# Sensors_AFE2.net
KiCad netlist of a schematic drawn in Altium Designer
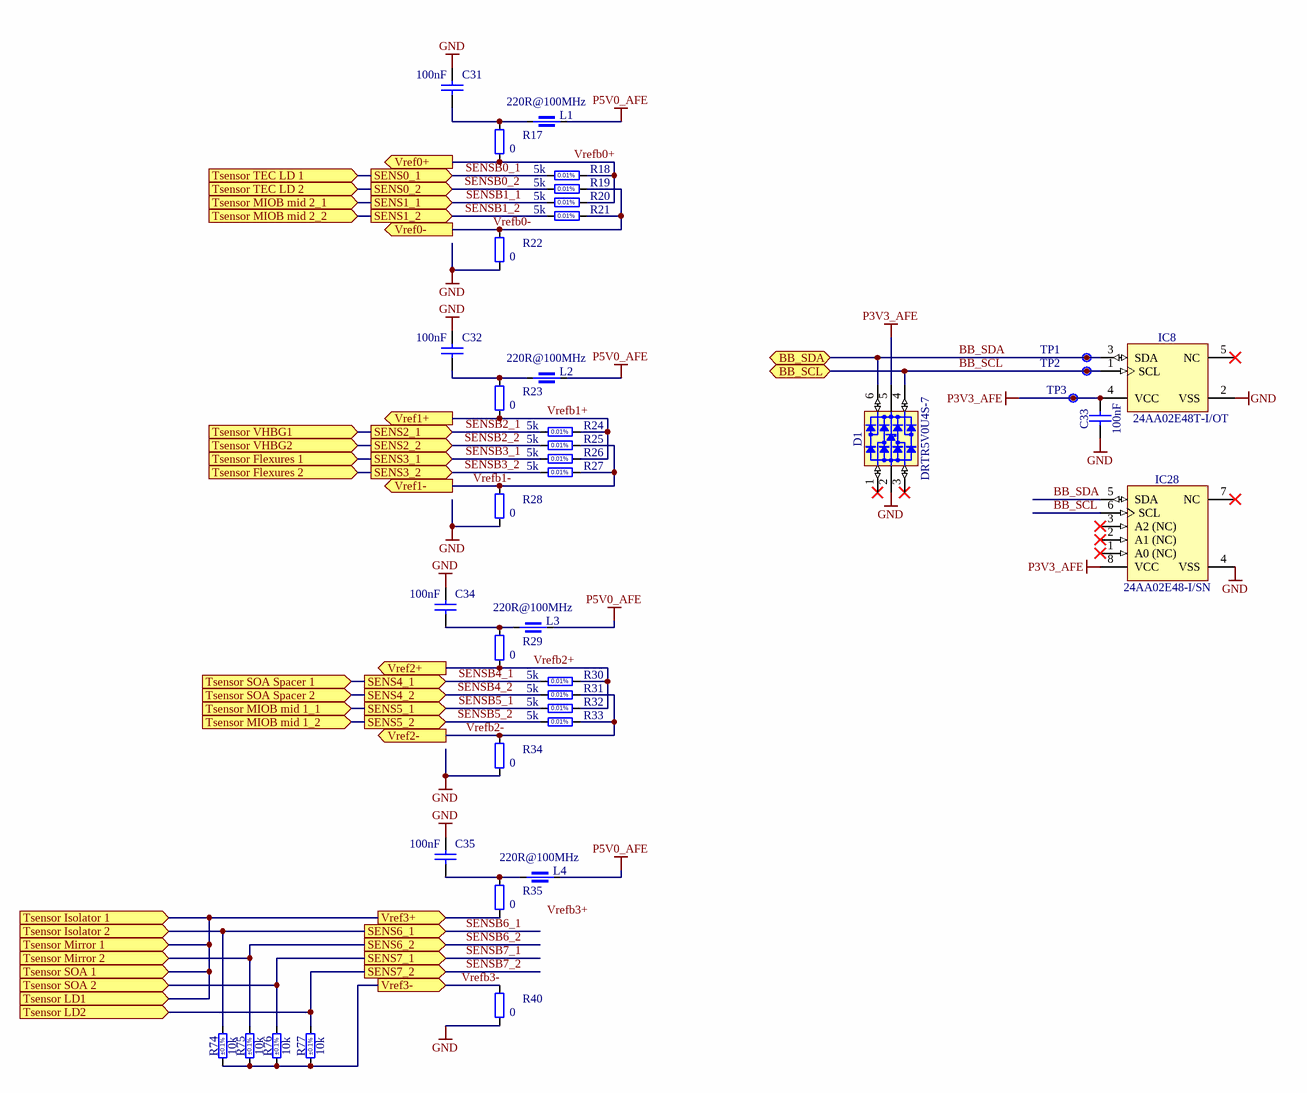
[diagram p0: Sensors_AFE2.schdoc]

(export (version "E")
  (design (tool "Eeschema 10.0.6"))
  (components
    (comp (ref "C31")
      (value "100nF")
      (footprint "CAPC1005X55N")
      (description "Non-polarised capacitor")
      (fields
        (field (name "PART NUMBER") "CC0402_100NF_16V_10%_X5R")
        (field (name "VOLTAGE") "16V")
        (field (name "AUTHOR") "CERN DEM JLC")
      )
      (libsource (lib "Capacitors") (part "Capacitor - non polarized"))
    )
    (comp (ref "C32")
      (value "100nF")
      (footprint "CAPC1005X55N")
      (description "Non-polarised capacitor")
      (fields
        (field (name "PART NUMBER") "CC0402_100NF_16V_10%_X5R")
        (field (name "VOLTAGE") "16V")
        (field (name "AUTHOR") "CERN DEM JLC")
      )
      (libsource (lib "Capacitors") (part "Capacitor - non polarized"))
    )
    (comp (ref "C33")
      (value "100nF")
      (footprint "CAPC1005X55N")
      (description "Non-polarised capacitor")
      (fields
        (field (name "PART NUMBER") "CC0402_100NF_16V_10%_X5R")
        (field (name "VOLTAGE") "16V")
        (field (name "AUTHOR") "CERN DEM JLC")
      )
      (libsource (lib "Capacitors") (part "Capacitor - non polarized"))
    )
    (comp (ref "C34")
      (value "100nF")
      (footprint "CAPC1005X55N")
      (description "Non-polarised capacitor")
      (fields
        (field (name "PART NUMBER") "CC0402_100NF_16V_10%_X5R")
        (field (name "VOLTAGE") "16V")
        (field (name "AUTHOR") "CERN DEM JLC")
      )
      (libsource (lib "Capacitors") (part "Capacitor - non polarized"))
    )
    (comp (ref "C35")
      (value "100nF")
      (footprint "CAPC1005X55N")
      (description "Non-polarised capacitor")
      (fields
        (field (name "PART NUMBER") "CC0402_100NF_16V_10%_X5R")
        (field (name "VOLTAGE") "16V")
        (field (name "AUTHOR") "CERN DEM JLC")
      )
      (libsource (lib "Capacitors") (part "Capacitor - non polarized"))
    )
    (comp (ref "D1")
      (value "DRTR5V0U4S-7")
      (footprint "SOT65P210X110-6N")
      (description "Integrated Quad Ultra-Low Capacitance ESD Protection")
      (fields (field (name "MANUFACTURER") "DIODES") (field (name "AUTHOR") "GK"))
      (libsource (lib "Diodes") (part "D_TVS_DRTR5V0U4S-7"))
    )
    (comp (ref "IC8")
      (value "24AA02E48T-I/OT")
      (footprint "SOT95P280X145-5N")
      (description "1.7V-5.5V, 2K I2C Serial EEPROM With EUI-48 Node Identity")
      (fields (field (name "MANUFACTURER") "MICROCHIP TECHNOLOGY") (field (name "AUTHOR") "CERN DEM MR"))
      (libsource (lib "ICs And Semiconductors") (part "24AA02E48T-I/OT"))
    )
    (comp (ref "IC28")
      (value "24AA02E48-I/SN")
      (footprint "SOIC127P600X175-8N")
      (description "1.7V-5.5V, 2K I2C™ Serial EEPROMs with EUI-48™ Node Identity")
      (fields (field (name "MANUFACTURER") "MICROCHIP TECHNOLOGY") (field (name "AUTHOR") "CERN DEM MR"))
      (libsource (lib "ICS-logic") (part "MEM_24AA02E48-I/SN"))
    )
    (comp (ref "L1")
      (value "220R@100MHz")
      (footprint "INDC1005X55N")
      (fields
        (field (name "PART NUMBER") "IND0402_MURATA_BLM15HB221SN1")
        (field (name "POWER") "250mA")
        (field (name "TOLERANCE") "±25%")
        (field (name "AUTHOR") "CERN DEM JLC")
      )
      (libsource (lib "Inductors & Transformers") (part "Ferrite Bead"))
    )
    (comp (ref "L2")
      (value "220R@100MHz")
      (footprint "INDC1005X55N")
      (fields
        (field (name "PART NUMBER") "IND0402_MURATA_BLM15HB221SN1")
        (field (name "POWER") "250mA")
        (field (name "TOLERANCE") "±25%")
        (field (name "AUTHOR") "CERN DEM JLC")
      )
      (libsource (lib "Inductors & Transformers") (part "Ferrite Bead"))
    )
    (comp (ref "L3")
      (value "220R@100MHz")
      (footprint "INDC1005X55N")
      (fields
        (field (name "PART NUMBER") "IND0402_MURATA_BLM15HB221SN1")
        (field (name "POWER") "250mA")
        (field (name "TOLERANCE") "±25%")
        (field (name "AUTHOR") "CERN DEM JLC")
      )
      (libsource (lib "Inductors & Transformers") (part "Ferrite Bead"))
    )
    (comp (ref "L4")
      (value "220R@100MHz")
      (footprint "INDC1005X55N")
      (fields
        (field (name "PART NUMBER") "IND0402_MURATA_BLM15HB221SN1")
        (field (name "POWER") "250mA")
        (field (name "TOLERANCE") "±25%")
        (field (name "AUTHOR") "CERN DEM JLC")
      )
      (libsource (lib "Inductors & Transformers") (part "Ferrite Bead"))
    )
    (comp (ref "R17")
      (value "0")
      (footprint "RESC1608X55N")
      (description "Resistor")
      (fields
        (field (name "PART NUMBER") "R0603_0R_JUMPER")
        (field (name "MANUFACTURER") "GENERIC")
        (field (name "AUTHOR") "CERN DEM JLC")
      )
      (libsource (lib "Resistors") (part "Resistor"))
    )
    (comp (ref "R18")
      (value "5k")
      (footprint "RESC2013X64N")
      (description "Resistor - 0.01%")
      (fields
        (field (name "PART NUMBER") "R0805_5K_0.01%_0.2W_0.2PPM_VISHAY_VSMP")
        (field (name "POWER") "0.2W")
        (field (name "AUTHOR") "CERN DEM JLC")
      )
      (libsource (lib "Resistors") (part "Resistor - 0.01%"))
    )
    (comp (ref "R19")
      (value "5k")
      (footprint "RESC2013X64N")
      (description "Resistor - 0.01%")
      (fields
        (field (name "PART NUMBER") "R0805_5K_0.01%_0.2W_0.2PPM_VISHAY_VSMP")
        (field (name "POWER") "0.2W")
        (field (name "AUTHOR") "CERN DEM JLC")
      )
      (libsource (lib "Resistors") (part "Resistor - 0.01%"))
    )
    (comp (ref "R20")
      (value "5k")
      (footprint "RESC2013X64N")
      (description "Resistor - 0.01%")
      (fields
        (field (name "PART NUMBER") "R0805_5K_0.01%_0.2W_0.2PPM_VISHAY_VSMP")
        (field (name "POWER") "0.2W")
        (field (name "AUTHOR") "CERN DEM JLC")
      )
      (libsource (lib "Resistors") (part "Resistor - 0.01%"))
    )
    (comp (ref "R21")
      (value "5k")
      (footprint "RESC2013X64N")
      (description "Resistor - 0.01%")
      (fields
        (field (name "PART NUMBER") "R0805_5K_0.01%_0.2W_0.2PPM_VISHAY_VSMP")
        (field (name "POWER") "0.2W")
        (field (name "AUTHOR") "CERN DEM JLC")
      )
      (libsource (lib "Resistors") (part "Resistor - 0.01%"))
    )
    (comp (ref "R22")
      (value "0")
      (footprint "RESC1608X55N")
      (description "Resistor")
      (fields
        (field (name "PART NUMBER") "R0603_0R_JUMPER")
        (field (name "MANUFACTURER") "GENERIC")
        (field (name "AUTHOR") "CERN DEM JLC")
      )
      (libsource (lib "Resistors") (part "Resistor"))
    )
    (comp (ref "R23")
      (value "0")
      (footprint "RESC1608X55N")
      (description "Resistor")
      (fields
        (field (name "PART NUMBER") "R0603_0R_JUMPER")
        (field (name "MANUFACTURER") "GENERIC")
        (field (name "AUTHOR") "CERN DEM JLC")
      )
      (libsource (lib "Resistors") (part "Resistor"))
    )
    (comp (ref "R24")
      (value "5k")
      (footprint "RESC2013X64N")
      (description "Resistor - 0.01%")
      (fields
        (field (name "PART NUMBER") "R0805_5K_0.01%_0.2W_0.2PPM_VISHAY_VSMP")
        (field (name "POWER") "0.2W")
        (field (name "AUTHOR") "CERN DEM JLC")
      )
      (libsource (lib "Resistors") (part "Resistor - 0.01%"))
    )
    (comp (ref "R25")
      (value "5k")
      (footprint "RESC2013X64N")
      (description "Resistor - 0.01%")
      (fields
        (field (name "PART NUMBER") "R0805_5K_0.01%_0.2W_0.2PPM_VISHAY_VSMP")
        (field (name "POWER") "0.2W")
        (field (name "AUTHOR") "CERN DEM JLC")
      )
      (libsource (lib "Resistors") (part "Resistor - 0.01%"))
    )
    (comp (ref "R26")
      (value "5k")
      (footprint "RESC2013X64N")
      (description "Resistor - 0.01%")
      (fields
        (field (name "PART NUMBER") "R0805_5K_0.01%_0.2W_0.2PPM_VISHAY_VSMP")
        (field (name "POWER") "0.2W")
        (field (name "AUTHOR") "CERN DEM JLC")
      )
      (libsource (lib "Resistors") (part "Resistor - 0.01%"))
    )
    (comp (ref "R27")
      (value "5k")
      (footprint "RESC2013X64N")
      (description "Resistor - 0.01%")
      (fields
        (field (name "PART NUMBER") "R0805_5K_0.01%_0.2W_0.2PPM_VISHAY_VSMP")
        (field (name "POWER") "0.2W")
        (field (name "AUTHOR") "CERN DEM JLC")
      )
      (libsource (lib "Resistors") (part "Resistor - 0.01%"))
    )
    (comp (ref "R28")
      (value "0")
      (footprint "RESC1608X55N")
      (description "Resistor")
      (fields
        (field (name "PART NUMBER") "R0603_0R_JUMPER")
        (field (name "MANUFACTURER") "GENERIC")
        (field (name "AUTHOR") "CERN DEM JLC")
      )
      (libsource (lib "Resistors") (part "Resistor"))
    )
    (comp (ref "R29")
      (value "0")
      (footprint "RESC1608X55N")
      (description "Resistor")
      (fields
        (field (name "PART NUMBER") "R0603_0R_JUMPER")
        (field (name "MANUFACTURER") "GENERIC")
        (field (name "AUTHOR") "CERN DEM JLC")
      )
      (libsource (lib "Resistors") (part "Resistor"))
    )
    (comp (ref "R30")
      (value "5k")
      (footprint "RESC2013X64N")
      (description "Resistor - 0.01%")
      (fields
        (field (name "PART NUMBER") "R0805_5K_0.01%_0.2W_0.2PPM_VISHAY_VSMP")
        (field (name "POWER") "0.2W")
        (field (name "AUTHOR") "CERN DEM JLC")
      )
      (libsource (lib "Resistors") (part "Resistor - 0.01%"))
    )
    (comp (ref "R31")
      (value "5k")
      (footprint "RESC2013X64N")
      (description "Resistor - 0.01%")
      (fields
        (field (name "PART NUMBER") "R0805_5K_0.01%_0.2W_0.2PPM_VISHAY_VSMP")
        (field (name "POWER") "0.2W")
        (field (name "AUTHOR") "CERN DEM JLC")
      )
      (libsource (lib "Resistors") (part "Resistor - 0.01%"))
    )
    (comp (ref "R32")
      (value "5k")
      (footprint "RESC2013X64N")
      (description "Resistor - 0.01%")
      (fields
        (field (name "PART NUMBER") "R0805_5K_0.01%_0.2W_0.2PPM_VISHAY_VSMP")
        (field (name "POWER") "0.2W")
        (field (name "AUTHOR") "CERN DEM JLC")
      )
      (libsource (lib "Resistors") (part "Resistor - 0.01%"))
    )
    (comp (ref "R33")
      (value "5k")
      (footprint "RESC2013X64N")
      (description "Resistor - 0.01%")
      (fields
        (field (name "PART NUMBER") "R0805_5K_0.01%_0.2W_0.2PPM_VISHAY_VSMP")
        (field (name "POWER") "0.2W")
        (field (name "AUTHOR") "CERN DEM JLC")
      )
      (libsource (lib "Resistors") (part "Resistor - 0.01%"))
    )
    (comp (ref "R34")
      (value "0")
      (footprint "RESC1608X55N")
      (description "Resistor")
      (fields
        (field (name "PART NUMBER") "R0603_0R_JUMPER")
        (field (name "MANUFACTURER") "GENERIC")
        (field (name "AUTHOR") "CERN DEM JLC")
      )
      (libsource (lib "Resistors") (part "Resistor"))
    )
    (comp (ref "R35")
      (value "0")
      (footprint "RESC1608X55N")
      (description "Resistor")
      (fields
        (field (name "PART NUMBER") "R0603_0R_JUMPER")
        (field (name "MANUFACTURER") "GENERIC")
        (field (name "AUTHOR") "CERN DEM JLC")
      )
      (libsource (lib "Resistors") (part "Resistor"))
    )
    (comp (ref "R40")
      (value "0")
      (footprint "RESC1608X55N")
      (description "Resistor")
      (fields
        (field (name "PART NUMBER") "R0603_0R_JUMPER")
        (field (name "MANUFACTURER") "GENERIC")
        (field (name "AUTHOR") "CERN DEM JLC")
      )
      (libsource (lib "Resistors") (part "Resistor"))
    )
    (comp (ref "R74")
      (value "10k")
      (footprint "RESC1608X55N")
      (description "Resistor - 0.1%")
      (fields
        (field (name "TOLERANCE") "±0.1%")
        (field (name "PART NUMBER") "R0603_10K_0.1%_0.063W_10PPM")
        (field (name "POWER") "0.063W")
        (field (name "AUTHOR") "CERN DEM JLC")
      )
      (libsource (lib "Resistors") (part "Resistor - 0.1%"))
    )
    (comp (ref "R75")
      (value "10k")
      (footprint "RESC1608X55N")
      (description "Resistor - 0.1%")
      (fields
        (field (name "TOLERANCE") "±0.1%")
        (field (name "PART NUMBER") "R0603_10K_0.1%_0.063W_10PPM")
        (field (name "POWER") "0.063W")
        (field (name "AUTHOR") "CERN DEM JLC")
      )
      (libsource (lib "Resistors") (part "Resistor - 0.1%"))
    )
    (comp (ref "R76")
      (value "10k")
      (footprint "RESC1608X55N")
      (description "Resistor - 0.1%")
      (fields
        (field (name "TOLERANCE") "±0.1%")
        (field (name "PART NUMBER") "R0603_10K_0.1%_0.063W_10PPM")
        (field (name "POWER") "0.063W")
        (field (name "AUTHOR") "CERN DEM JLC")
      )
      (libsource (lib "Resistors") (part "Resistor - 0.1%"))
    )
    (comp (ref "R77")
      (value "10k")
      (footprint "RESC1608X55N")
      (description "Resistor - 0.1%")
      (fields
        (field (name "TOLERANCE") "±0.1%")
        (field (name "PART NUMBER") "R0603_10K_0.1%_0.063W_10PPM")
        (field (name "POWER") "0.063W")
        (field (name "AUTHOR") "CERN DEM JLC")
      )
      (libsource (lib "Resistors") (part "Resistor - 0.1%"))
    )
    (comp (ref "TP1")
      (value "Test Point")
      (footprint "TPS127")
      (fields (field (name "PART NUMBER") "SMD_PAD_1.27X1.27MM") (field (name "AUTHOR") "CERN DEM JLC"))
      (libsource (lib "Eletro-mechanical") (part "Test Point"))
    )
    (comp (ref "TP2")
      (value "Test Point")
      (footprint "TPS127")
      (fields (field (name "PART NUMBER") "SMD_PAD_1.27X1.27MM") (field (name "AUTHOR") "CERN DEM JLC"))
      (libsource (lib "Eletro-mechanical") (part "Test Point"))
    )
    (comp (ref "TP3")
      (value "Test Point")
      (footprint "TPS127")
      (fields (field (name "PART NUMBER") "SMD_PAD_1.27X1.27MM") (field (name "AUTHOR") "CERN DEM JLC"))
      (libsource (lib "Eletro-mechanical") (part "Test Point"))
    )
  )
  (nets
    (net (code "1") (name "/BB_SCL") (class "Default")
      (node (ref "D1") (pin "4") (pinfunction "I/O3_4") (pintype "bidirectional"))
      (node (ref "IC28") (pin "6") (pinfunction "SCL_6") (pintype "input"))
      (node (ref "IC8") (pin "1") (pinfunction "SCL_1") (pintype "input"))
      (node (ref "TP2") (pin "1") (pinfunction "1_1") (pintype "bidirectional"))
    )
    (net (code "2") (name "/BB_SDA") (class "Default")
      (node (ref "D1") (pin "6") (pinfunction "I/O4_6") (pintype "bidirectional"))
      (node (ref "IC28") (pin "5") (pinfunction "SDA_5") (pintype "bidirectional"))
      (node (ref "IC8") (pin "3") (pinfunction "SDA_3") (pintype "bidirectional"))
      (node (ref "TP1") (pin "1") (pinfunction "1_1") (pintype "bidirectional"))
    )
    (net (code "3") (name "/SENSB0_1") (class "Default")
      (node (ref "R18") (pin "1") (pinfunction "1_1") (pintype "passive"))
    )
    (net (code "4") (name "/SENSB0_2") (class "Default")
      (node (ref "R19") (pin "1") (pinfunction "1_1") (pintype "passive"))
    )
    (net (code "5") (name "/SENSB1_1") (class "Default")
      (node (ref "R20") (pin "1") (pinfunction "1_1") (pintype "passive"))
    )
    (net (code "6") (name "/SENSB1_2") (class "Default")
      (node (ref "R21") (pin "1") (pinfunction "1_1") (pintype "passive"))
    )
    (net (code "7") (name "/SENSB2_1") (class "Default")
      (node (ref "R24") (pin "1") (pinfunction "1_1") (pintype "passive"))
    )
    (net (code "8") (name "/SENSB2_2") (class "Default")
      (node (ref "R25") (pin "1") (pinfunction "1_1") (pintype "passive"))
    )
    (net (code "9") (name "/SENSB3_1") (class "Default")
      (node (ref "R26") (pin "1") (pinfunction "1_1") (pintype "passive"))
    )
    (net (code "10") (name "/SENSB3_2") (class "Default")
      (node (ref "R27") (pin "1") (pinfunction "1_1") (pintype "passive"))
    )
    (net (code "11") (name "/SENSB4_1") (class "Default")
      (node (ref "R30") (pin "1") (pinfunction "1_1") (pintype "passive"))
    )
    (net (code "12") (name "/SENSB4_2") (class "Default")
      (node (ref "R31") (pin "1") (pinfunction "1_1") (pintype "passive"))
    )
    (net (code "13") (name "/SENSB5_1") (class "Default")
      (node (ref "R32") (pin "1") (pinfunction "1_1") (pintype "passive"))
    )
    (net (code "14") (name "/SENSB5_2") (class "Default")
      (node (ref "R33") (pin "1") (pinfunction "1_1") (pintype "passive"))
    )
    (net (code "15") (name "/SENSB6_1") (class "Default")
      (node (ref "R74") (pin "2") (pinfunction "2_2") (pintype "passive"))
    )
    (net (code "16") (name "/SENSB6_2") (class "Default")
      (node (ref "R75") (pin "2") (pinfunction "2_2") (pintype "passive"))
    )
    (net (code "17") (name "/SENSB7_1") (class "Default")
      (node (ref "R76") (pin "2") (pinfunction "2_2") (pintype "passive"))
    )
    (net (code "18") (name "/SENSB7_2") (class "Default")
      (node (ref "R77") (pin "2") (pinfunction "2_2") (pintype "passive"))
    )
    (net (code "19") (name "/Tsensor Isolator 1") (class "Default")
      (node (ref "R35") (pin "1") (pinfunction "1_1") (pintype "passive"))
    )
    (net (code "20") (name "/Vrefb0+") (class "Default")
      (node (ref "R17") (pin "1") (pinfunction "1_1") (pintype "passive"))
      (node (ref "R18") (pin "2") (pinfunction "2_2") (pintype "passive"))
      (node (ref "R20") (pin "2") (pinfunction "2_2") (pintype "passive"))
    )
    (net (code "21") (name "/Vrefb0-") (class "Default")
      (node (ref "R19") (pin "2") (pinfunction "2_2") (pintype "passive"))
      (node (ref "R21") (pin "2") (pinfunction "2_2") (pintype "passive"))
      (node (ref "R22") (pin "2") (pinfunction "2_2") (pintype "passive"))
    )
    (net (code "22") (name "/Vrefb1+") (class "Default")
      (node (ref "R23") (pin "1") (pinfunction "1_1") (pintype "passive"))
      (node (ref "R24") (pin "2") (pinfunction "2_2") (pintype "passive"))
      (node (ref "R26") (pin "2") (pinfunction "2_2") (pintype "passive"))
    )
    (net (code "23") (name "/Vrefb1-") (class "Default")
      (node (ref "R25") (pin "2") (pinfunction "2_2") (pintype "passive"))
      (node (ref "R27") (pin "2") (pinfunction "2_2") (pintype "passive"))
      (node (ref "R28") (pin "2") (pinfunction "2_2") (pintype "passive"))
    )
    (net (code "24") (name "/Vrefb2+") (class "Default")
      (node (ref "R29") (pin "1") (pinfunction "1_1") (pintype "passive"))
      (node (ref "R30") (pin "2") (pinfunction "2_2") (pintype "passive"))
      (node (ref "R32") (pin "2") (pinfunction "2_2") (pintype "passive"))
    )
    (net (code "25") (name "/Vrefb2-") (class "Default")
      (node (ref "R31") (pin "2") (pinfunction "2_2") (pintype "passive"))
      (node (ref "R33") (pin "2") (pinfunction "2_2") (pintype "passive"))
      (node (ref "R34") (pin "2") (pinfunction "2_2") (pintype "passive"))
    )
    (net (code "27") (name "/Vrefb3-") (class "Default")
      (node (ref "R40") (pin "2") (pinfunction "2_2") (pintype "passive"))
      (node (ref "R74") (pin "1") (pinfunction "1_1") (pintype "passive"))
      (node (ref "R75") (pin "1") (pinfunction "1_1") (pintype "passive"))
      (node (ref "R76") (pin "1") (pinfunction "1_1") (pintype "passive"))
      (node (ref "R77") (pin "1") (pinfunction "1_1") (pintype "passive"))
    )
    (net (code "28") (name "GND") (class "Default")
      (node (ref "C31") (pin "1") (pinfunction "1_1") (pintype "passive"))
      (node (ref "C32") (pin "1") (pinfunction "1_1") (pintype "passive"))
      (node (ref "C33") (pin "1") (pinfunction "1_1") (pintype "passive"))
      (node (ref "C34") (pin "1") (pinfunction "1_1") (pintype "passive"))
      (node (ref "C35") (pin "1") (pinfunction "1_1") (pintype "passive"))
      (node (ref "D1") (pin "2") (pinfunction "GND_2") (pintype "power_in"))
      (node (ref "IC28") (pin "4") (pinfunction "VSS_4") (pintype "power_in"))
      (node (ref "IC8") (pin "2") (pinfunction "VSS_2") (pintype "power_in"))
      (node (ref "R22") (pin "1") (pinfunction "1_1") (pintype "passive"))
      (node (ref "R28") (pin "1") (pinfunction "1_1") (pintype "passive"))
      (node (ref "R34") (pin "1") (pinfunction "1_1") (pintype "passive"))
      (node (ref "R40") (pin "1") (pinfunction "1_1") (pintype "passive"))
    )
    (net (code "29") (name "Net-(C31-Pad2)") (class "Default")
      (node (ref "C31") (pin "2") (pinfunction "2_2") (pintype "passive"))
      (node (ref "L1") (pin "1") (pinfunction "1_1") (pintype "passive"))
      (node (ref "R17") (pin "2") (pinfunction "2_2") (pintype "passive"))
    )
    (net (code "30") (name "Net-(C32-Pad2)") (class "Default")
      (node (ref "C32") (pin "2") (pinfunction "2_2") (pintype "passive"))
      (node (ref "L2") (pin "1") (pinfunction "1_1") (pintype "passive"))
      (node (ref "R23") (pin "2") (pinfunction "2_2") (pintype "passive"))
    )
    (net (code "31") (name "Net-(C34-Pad2)") (class "Default")
      (node (ref "C34") (pin "2") (pinfunction "2_2") (pintype "passive"))
      (node (ref "L3") (pin "1") (pinfunction "1_1") (pintype "passive"))
      (node (ref "R29") (pin "2") (pinfunction "2_2") (pintype "passive"))
    )
    (net (code "32") (name "Net-(C35-Pad2)") (class "Default")
      (node (ref "C35") (pin "2") (pinfunction "2_2") (pintype "passive"))
      (node (ref "L4") (pin "1") (pinfunction "1_1") (pintype "passive"))
      (node (ref "R35") (pin "2") (pinfunction "2_2") (pintype "passive"))
    )
    (net (code "33") (name "P3V3_AFE") (class "Default")
      (node (ref "C33") (pin "2") (pinfunction "2_2") (pintype "passive"))
      (node (ref "D1") (pin "5") (pinfunction "VBUS_5") (pintype "power_in"))
      (node (ref "IC28") (pin "8") (pinfunction "VCC_8") (pintype "power_in"))
      (node (ref "IC8") (pin "4") (pinfunction "VCC_4") (pintype "power_in"))
      (node (ref "TP3") (pin "1") (pinfunction "1_1") (pintype "bidirectional"))
    )
    (net (code "34") (name "P5V0_AFE") (class "Default")
      (node (ref "L1") (pin "2") (pinfunction "2_2") (pintype "passive"))
      (node (ref "L2") (pin "2") (pinfunction "2_2") (pintype "passive"))
      (node (ref "L3") (pin "2") (pinfunction "2_2") (pintype "passive"))
      (node (ref "L4") (pin "2") (pinfunction "2_2") (pintype "passive"))
    )
    (net (code "35") (name "unconnected-(D1-I{slash}O1-Pad1)") (class "Default")
      (node (ref "D1") (pin "1") (pinfunction "I/O1_1") (pintype "bidirectional+no_connect"))
    )
    (net (code "36") (name "unconnected-(D1-I{slash}O2-Pad3)") (class "Default")
      (node (ref "D1") (pin "3") (pinfunction "I/O2_3") (pintype "bidirectional+no_connect"))
    )
    (net (code "37") (name "unconnected-(IC8-NC-Pad5)") (class "Default")
      (node (ref "IC8") (pin "5") (pinfunction "NC_5") (pintype "passive+no_connect"))
    )
    (net (code "38") (name "unconnected-(IC28-A0_(NC)-Pad1)") (class "Default")
      (node (ref "IC28") (pin "1") (pinfunction "A0_(NC)_1") (pintype "input+no_connect"))
    )
    (net (code "39") (name "unconnected-(IC28-A1_(NC)-Pad2)") (class "Default")
      (node (ref "IC28") (pin "2") (pinfunction "A1_(NC)_2") (pintype "input+no_connect"))
    )
    (net (code "40") (name "unconnected-(IC28-A2_(NC)-Pad3)") (class "Default")
      (node (ref "IC28") (pin "3") (pinfunction "A2_(NC)_3") (pintype "input+no_connect"))
    )
    (net (code "41") (name "unconnected-(IC28-NC-Pad7)") (class "Default")
      (node (ref "IC28") (pin "7") (pinfunction "NC_7") (pintype "passive+no_connect"))
    )
  )
)
